# puck.net
KiCad netlist of a schematic drawn in EAGLE
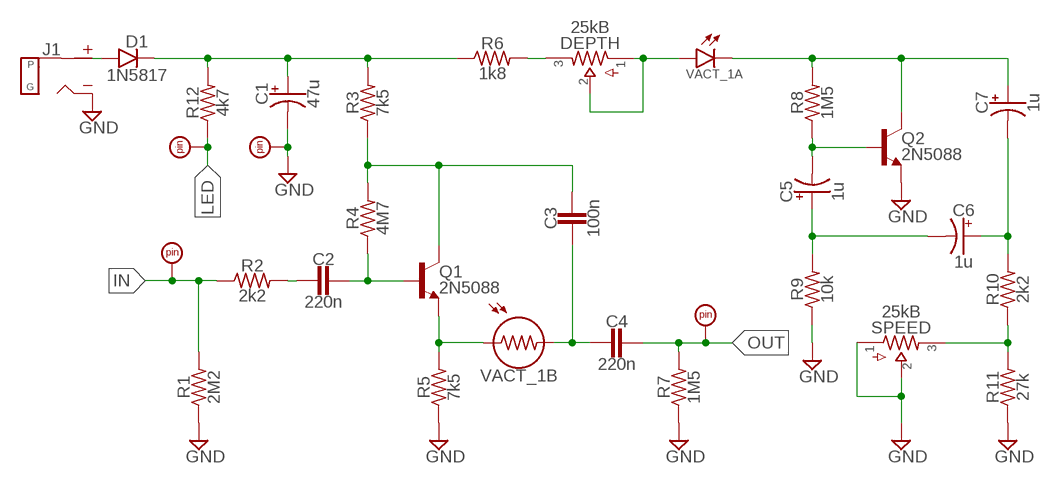
[diagram p0: schematic, sheet 1]

(export (version "E")
  (design (tool "Eeschema 10.0.6"))
  (components
    (comp (ref "C1")
      (value "47u")
      (footprint "eagle-import:050_020_1")
      (libsource (lib "eagle-import") (part "0501"))
    )
    (comp (ref "C2")
      (value "220n")
      (footprint "eagle-import:050X030_025_2")
      (libsource (lib "eagle-import") (part "CER/FILM2"))
    )
    (comp (ref "C3")
      (value "100n")
      (footprint "eagle-import:050X030_025_2")
      (libsource (lib "eagle-import") (part "CER/FILM2"))
    )
    (comp (ref "C4")
      (value "220n")
      (footprint "eagle-import:050X030_025_2")
      (libsource (lib "eagle-import") (part "CER/FILM2"))
    )
    (comp (ref "C5")
      (value "1u")
      (footprint "eagle-import:050_020")
      (libsource (lib "eagle-import") (part "0500"))
    )
    (comp (ref "C6")
      (value "1u")
      (footprint "eagle-import:050_020")
      (libsource (lib "eagle-import") (part "0500"))
    )
    (comp (ref "C7")
      (value "1u")
      (footprint "eagle-import:050_020")
      (libsource (lib "eagle-import") (part "0500"))
    )
    (comp (ref "D1")
      (value "1N5817")
      (footprint "eagle-import:DO41-3")
      (libsource (lib "eagle-import") (part "DO41.3"))
    )
    (comp (ref "DEPTH")
      (value "25kB")
      (footprint "eagle-import:2262_TRIM")
      (libsource (lib "eagle-import") (part "POTSTRIM"))
    )
    (comp (ref "GND")
      (value "PADRND")
      (footprint "eagle-import:ROUND")
      (libsource (lib "eagle-import") (part "PADRND"))
    )
    (comp (ref "IN")
      (value "PADSQR")
      (footprint "eagle-import:SQUARE")
      (libsource (lib "eagle-import") (part "PADSQR"))
    )
    (comp (ref "J1")
      (value "DC_MONO")
      (footprint "eagle-import:DC")
      (libsource (lib "eagle-import") (part "DC_MONO"))
    )
    (comp (ref "LED")
      (value "PADRND")
      (footprint "eagle-import:ROUND")
      (libsource (lib "eagle-import") (part "PADRND"))
    )
    (comp (ref "OUT")
      (value "PADSQR")
      (footprint "eagle-import:SQUARE")
      (libsource (lib "eagle-import") (part "PADSQR"))
    )
    (comp (ref "Q1")
      (value "2N5088")
      (footprint "eagle-import:TO92-")
      (libsource (lib "eagle-import") (part "2N5088"))
    )
    (comp (ref "Q2")
      (value "2N5088")
      (footprint "eagle-import:TO92-")
      (libsource (lib "eagle-import") (part "2N5088"))
    )
    (comp (ref "R1")
      (value "2M2")
      (footprint "eagle-import:R0207_3")
      (libsource (lib "eagle-import") (part "R_.3B"))
    )
    (comp (ref "R2")
      (value "2k2")
      (footprint "eagle-import:R0207_3")
      (libsource (lib "eagle-import") (part "R_.3B"))
    )
    (comp (ref "R3")
      (value "7k5")
      (footprint "eagle-import:R0207_3")
      (libsource (lib "eagle-import") (part "R_.3B"))
    )
    (comp (ref "R4")
      (value "4M7")
      (footprint "eagle-import:R0207_3")
      (libsource (lib "eagle-import") (part "R_.3B"))
    )
    (comp (ref "R5")
      (value "7k5")
      (footprint "eagle-import:R0207_3")
      (libsource (lib "eagle-import") (part "R_.3B"))
    )
    (comp (ref "R6")
      (value "1k8")
      (footprint "eagle-import:R0207_3")
      (libsource (lib "eagle-import") (part "R_.3B"))
    )
    (comp (ref "R7")
      (value "1M5")
      (footprint "eagle-import:R0207_3")
      (libsource (lib "eagle-import") (part "R_.3B"))
    )
    (comp (ref "R8")
      (value "1M5")
      (footprint "eagle-import:R0207_3")
      (libsource (lib "eagle-import") (part "R_.3B"))
    )
    (comp (ref "R9")
      (value "10k")
      (footprint "eagle-import:R0207_3")
      (libsource (lib "eagle-import") (part "R_.3B"))
    )
    (comp (ref "R10")
      (value "2k2")
      (footprint "eagle-import:R0207_3")
      (libsource (lib "eagle-import") (part "R_.3B"))
    )
    (comp (ref "R11")
      (value "27k")
      (footprint "eagle-import:R0207_3")
      (libsource (lib "eagle-import") (part "R_.3B"))
    )
    (comp (ref "R12")
      (value "4k7")
      (footprint "eagle-import:R0207_3")
      (libsource (lib "eagle-import") (part "R_.3B"))
    )
    (comp (ref "SPEED")
      (value "25kB")
      (footprint "eagle-import:PADS_SMALL")
      (libsource (lib "eagle-import") (part "POTSSMALL_PADS"))
    )
    (comp (ref "VACT_1")
      (value "VACTROL")
      (footprint "eagle-import:_LDR")
      (libsource (lib "eagle-import") (part "VACTROL"))
    )
  )
  (nets
    (net (code "1") (name "GND") (class "Default")
      (node (ref "C1") (pin "-") (pinfunction "-_-") (pintype "passive"))
      (node (ref "GND") (pin "1") (pinfunction "P$1_1") (pintype "bidirectional"))
      (node (ref "J1") (pin "S") (pinfunction "SLEEVE_S") (pintype "passive"))
      (node (ref "Q2") (pin "3") (pinfunction "E_3") (pintype "passive"))
      (node (ref "R1") (pin "1") (pinfunction "1_1") (pintype "passive"))
      (node (ref "R11") (pin "1") (pinfunction "1_1") (pintype "passive"))
      (node (ref "R5") (pin "1") (pinfunction "1_1") (pintype "passive"))
      (node (ref "R7") (pin "1") (pinfunction "1_1") (pintype "passive"))
      (node (ref "R9") (pin "1") (pinfunction "1_1") (pintype "passive"))
      (node (ref "SPEED") (pin "1") (pinfunction "1_1") (pintype "passive"))
      (node (ref "SPEED") (pin "2") (pinfunction "2_2") (pintype "passive"))
    )
    (net (code "2") (name "IN") (class "Default")
      (node (ref "IN") (pin "1") (pinfunction "P$1_1") (pintype "bidirectional"))
      (node (ref "R1") (pin "2") (pinfunction "2_2") (pintype "passive"))
      (node (ref "R2") (pin "1") (pinfunction "1_1") (pintype "passive"))
    )
    (net (code "3") (name "LED") (class "Default")
      (node (ref "LED") (pin "1") (pinfunction "P$1_1") (pintype "bidirectional"))
      (node (ref "R12") (pin "1") (pinfunction "1_1") (pintype "passive"))
    )
    (net (code "4") (name "Net-(C1-Pad+)") (class "Default")
      (node (ref "C1") (pin "+") (pinfunction "+_+") (pintype "passive"))
      (node (ref "D1") (pin "C") (pinfunction "C_C") (pintype "passive"))
      (node (ref "R12") (pin "2") (pinfunction "2_2") (pintype "passive"))
      (node (ref "R3") (pin "2") (pinfunction "2_2") (pintype "passive"))
      (node (ref "R6") (pin "1") (pinfunction "1_1") (pintype "passive"))
    )
    (net (code "5") (name "Net-(C2-Pad2)") (class "Default")
      (node (ref "C2") (pin "2") (pinfunction "2_2") (pintype "passive"))
      (node (ref "R2") (pin "2") (pinfunction "2_2") (pintype "passive"))
    )
    (net (code "6") (name "Net-(C3-Pad2)") (class "Default")
      (node (ref "C3") (pin "2") (pinfunction "2_2") (pintype "passive"))
      (node (ref "C4") (pin "2") (pinfunction "2_2") (pintype "passive"))
      (node (ref "VACT_1") (pin "2") (pinfunction "2_2") (pintype "passive"))
    )
    (net (code "7") (name "Net-(C5-Pad+)") (class "Default")
      (node (ref "C5") (pin "+") (pinfunction "+_+") (pintype "passive"))
      (node (ref "C6") (pin "-") (pinfunction "-_-") (pintype "passive"))
      (node (ref "R9") (pin "2") (pinfunction "2_2") (pintype "passive"))
    )
    (net (code "8") (name "Net-(C6-Pad+)") (class "Default")
      (node (ref "C6") (pin "+") (pinfunction "+_+") (pintype "passive"))
      (node (ref "C7") (pin "-") (pinfunction "-_-") (pintype "passive"))
      (node (ref "R10") (pin "2") (pinfunction "2_2") (pintype "passive"))
    )
    (net (code "9") (name "Net-(DEPTH-Pad1)") (class "Default")
      (node (ref "DEPTH") (pin "1") (pinfunction "1_1") (pintype "passive"))
      (node (ref "DEPTH") (pin "2") (pinfunction "2_2") (pintype "passive"))
      (node (ref "VACT_1") (pin "ANODE") (pinfunction "ANODE_ANODE") (pintype "passive"))
    )
    (net (code "10") (name "Net-(DEPTH-Pad3)") (class "Default")
      (node (ref "DEPTH") (pin "3") (pinfunction "3_3") (pintype "passive"))
      (node (ref "R6") (pin "2") (pinfunction "2_2") (pintype "passive"))
    )
    (net (code "11") (name "Net-(J1-TIP)") (class "Default")
      (node (ref "D1") (pin "A") (pinfunction "A_A") (pintype "passive"))
      (node (ref "J1") (pin "T") (pinfunction "TIP_T") (pintype "passive"))
    )
    (net (code "12") (name "Net-(Q1-B)") (class "Default")
      (node (ref "C2") (pin "1") (pinfunction "1_1") (pintype "passive"))
      (node (ref "Q1") (pin "2") (pinfunction "B_2") (pintype "passive"))
      (node (ref "R4") (pin "1") (pinfunction "1_1") (pintype "passive"))
    )
    (net (code "13") (name "Net-(Q1-C)") (class "Default")
      (node (ref "C3") (pin "1") (pinfunction "1_1") (pintype "passive"))
      (node (ref "Q1") (pin "1") (pinfunction "C_1") (pintype "passive"))
      (node (ref "R3") (pin "1") (pinfunction "1_1") (pintype "passive"))
      (node (ref "R4") (pin "2") (pinfunction "2_2") (pintype "passive"))
    )
    (net (code "14") (name "Net-(Q1-E)") (class "Default")
      (node (ref "Q1") (pin "3") (pinfunction "E_3") (pintype "passive"))
      (node (ref "R5") (pin "2") (pinfunction "2_2") (pintype "passive"))
      (node (ref "VACT_1") (pin "1") (pinfunction "1_1") (pintype "passive"))
    )
    (net (code "15") (name "Net-(Q2-B)") (class "Default")
      (node (ref "C5") (pin "-") (pinfunction "-_-") (pintype "passive"))
      (node (ref "Q2") (pin "2") (pinfunction "B_2") (pintype "passive"))
      (node (ref "R8") (pin "1") (pinfunction "1_1") (pintype "passive"))
    )
    (net (code "16") (name "Net-(Q2-C)") (class "Default")
      (node (ref "C7") (pin "+") (pinfunction "+_+") (pintype "passive"))
      (node (ref "Q2") (pin "1") (pinfunction "C_1") (pintype "passive"))
      (node (ref "R8") (pin "2") (pinfunction "2_2") (pintype "passive"))
      (node (ref "VACT_1") (pin "CATHODE") (pinfunction "CATHODE_CATHODE") (pintype "passive"))
    )
    (net (code "17") (name "Net-(R10-Pad1)") (class "Default")
      (node (ref "R10") (pin "1") (pinfunction "1_1") (pintype "passive"))
      (node (ref "R11") (pin "2") (pinfunction "2_2") (pintype "passive"))
      (node (ref "SPEED") (pin "3") (pinfunction "3_3") (pintype "passive"))
    )
    (net (code "18") (name "OUT") (class "Default")
      (node (ref "C4") (pin "1") (pinfunction "1_1") (pintype "passive"))
      (node (ref "OUT") (pin "1") (pinfunction "P$1_1") (pintype "bidirectional"))
      (node (ref "R7") (pin "2") (pinfunction "2_2") (pintype "passive"))
    )
  )
)
